# 1_Sheet_1_schdoc.net
KiCad netlist of a schematic drawn in Altium Designer
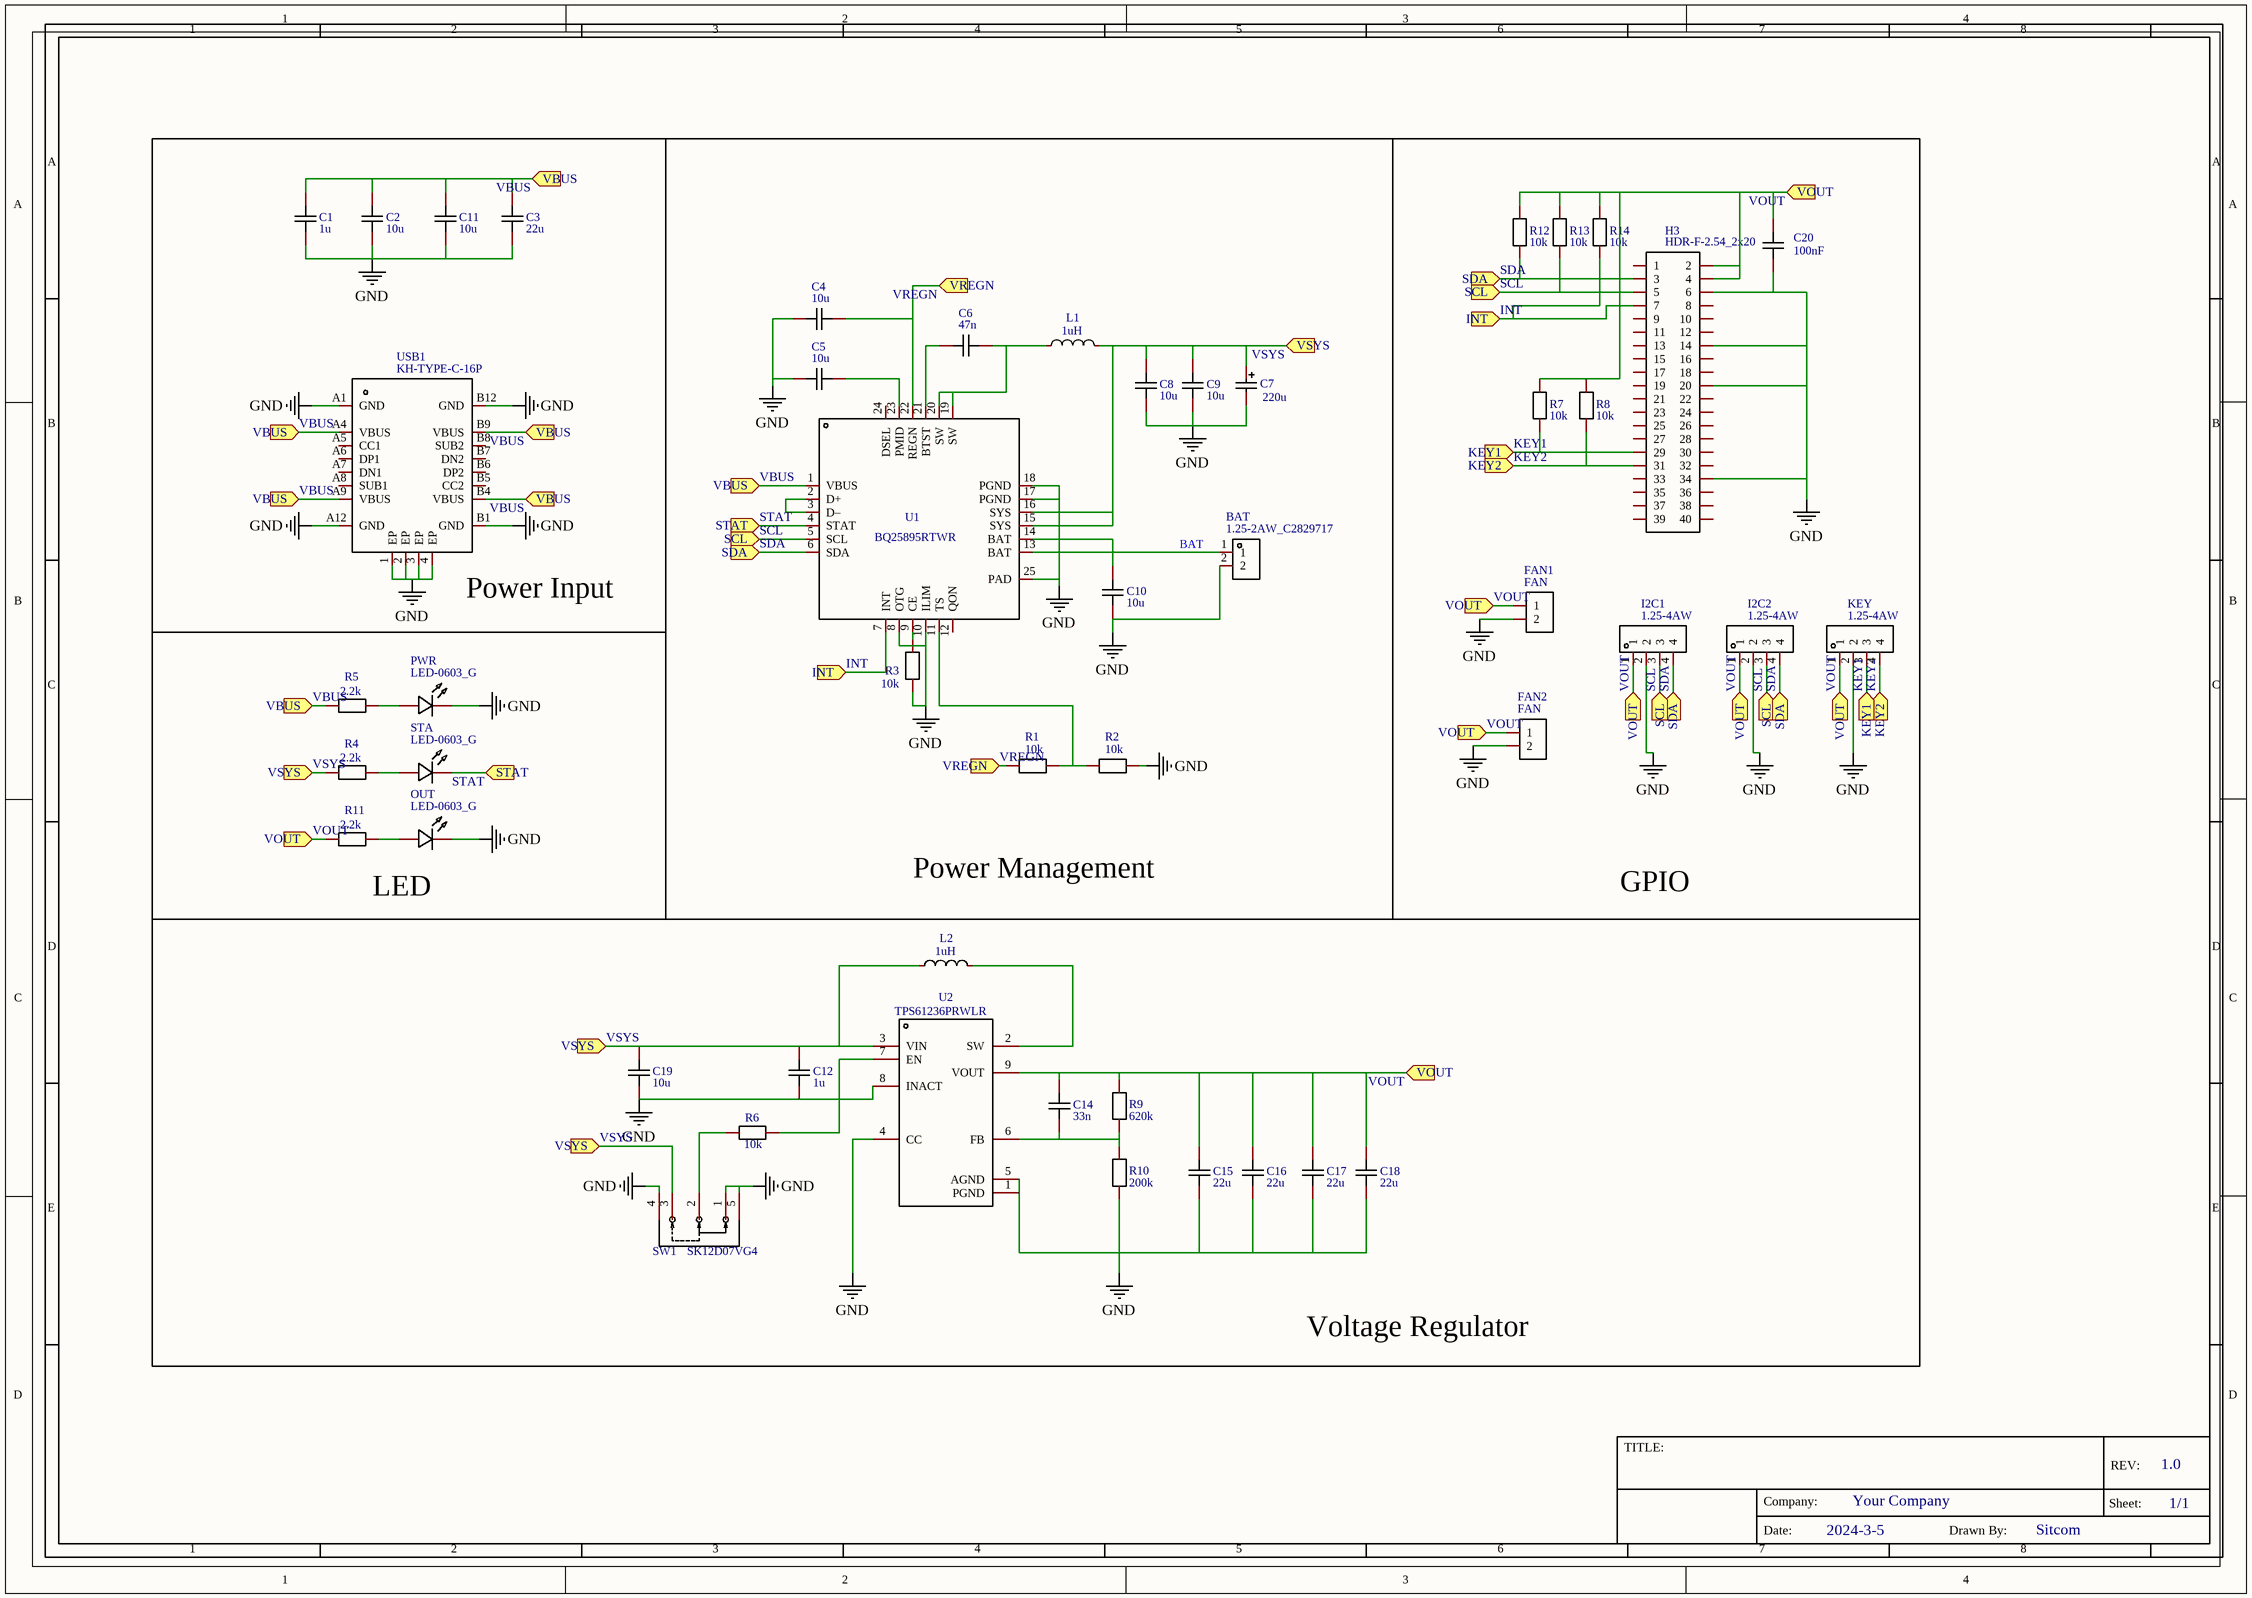
[diagram p0: 1_Sheet_1.schdoc.schdoc]

(export (version "E")
  (design (tool "Eeschema 10.0.6"))
  (components
    (comp (ref "BAT")
      (value "1.25-2AW_C2829717")
      (fields
        (field (name "NAME") "1.25-2AW_C2829717")
        (field (name "MANUFACTURER") "FG(富港)")
        (field (name "MANUFACTURER PART") "1.25-2AW")
      )
      (libsource (lib "altium-import") (part "root_0_1.25-2AW_"))
    )
    (comp (ref "C1")
      (value "1u")
      (fields (field (name "NAME") "1u"))
      (libsource (lib "altium-import") (part "root_1_1u_"))
    )
    (comp (ref "C2")
      (value "10u")
      (fields (field (name "NAME") "10u"))
      (libsource (lib "altium-import") (part "root_1_10u_"))
    )
    (comp (ref "C3")
      (value "22u")
      (fields (field (name "NAME") "22u"))
      (libsource (lib "altium-import") (part "root_1_22u_"))
    )
    (comp (ref "C4")
      (value "10u")
      (fields (field (name "NAME") "10u"))
      (libsource (lib "altium-import") (part "root_2_10u_"))
    )
    (comp (ref "C5")
      (value "10u")
      (fields (field (name "NAME") "10u"))
      (libsource (lib "altium-import") (part "root_2_10u_"))
    )
    (comp (ref "C6")
      (value "47n")
      (fields (field (name "NAME") "47n"))
      (libsource (lib "altium-import") (part "root_0_47n_"))
    )
    (comp (ref "C7")
      (value "220u")
      (fields
        (field (name "NAME") "220u")
        (field (name "MANUFACTURER") "AVX")
        (field (name "MANUFACTURER PART") "TAJB107M006RNJ")
      )
      (libsource (lib "altium-import") (part "root_1_TAJB107M006RNJ_"))
    )
    (comp (ref "C8")
      (value "10u")
      (fields (field (name "NAME") "10u"))
      (libsource (lib "altium-import") (part "root_1_10u_"))
    )
    (comp (ref "C9")
      (value "10u")
      (fields (field (name "NAME") "10u"))
      (libsource (lib "altium-import") (part "root_1_10u_"))
    )
    (comp (ref "C10")
      (value "10u")
      (fields (field (name "NAME") "10u"))
      (libsource (lib "altium-import") (part "root_1_10u_"))
    )
    (comp (ref "C11")
      (value "10u")
      (fields (field (name "NAME") "10u"))
      (libsource (lib "altium-import") (part "root_1_10u_"))
    )
    (comp (ref "C12")
      (value "1u")
      (fields (field (name "NAME") "1u"))
      (libsource (lib "altium-import") (part "root_1_1u_"))
    )
    (comp (ref "C14")
      (value "33n")
      (fields (field (name "NAME") "33n"))
      (libsource (lib "altium-import") (part "root_1_33n_"))
    )
    (comp (ref "C15")
      (value "22u")
      (fields (field (name "NAME") "22u"))
      (libsource (lib "altium-import") (part "root_1_22u_"))
    )
    (comp (ref "C16")
      (value "22u")
      (fields (field (name "NAME") "22u"))
      (libsource (lib "altium-import") (part "root_1_22u_"))
    )
    (comp (ref "C17")
      (value "22u")
      (fields (field (name "NAME") "22u"))
      (libsource (lib "altium-import") (part "root_1_22u_"))
    )
    (comp (ref "C18")
      (value "22u")
      (fields (field (name "NAME") "22u"))
      (libsource (lib "altium-import") (part "root_1_22u_"))
    )
    (comp (ref "C19")
      (value "10u")
      (fields (field (name "NAME") "10u"))
      (libsource (lib "altium-import") (part "root_1_10u_"))
    )
    (comp (ref "C20")
      (value "100nF")
      (fields (field (name "NAME") "100nF"))
      (libsource (lib "altium-import") (part "root_1_mirrored_CAP_0603_"))
    )
    (comp (ref "FAN1")
      (value "FAN")
      (fields (field (name "NAME") "FAN"))
      (libsource (lib "altium-import") (part "root_0_FAN_"))
    )
    (comp (ref "FAN2")
      (value "FAN")
      (fields (field (name "NAME") "FAN"))
      (libsource (lib "altium-import") (part "root_0_FAN_"))
    )
    (comp (ref "H3")
      (value "HDR-F-2.54_2x20")
      (fields (field (name "NAME") "HDR-F-2.54_2x20"))
      (libsource (lib "altium-import") (part "root_0_HDR-F-2.54_2x20_"))
    )
    (comp (ref "I2C1")
      (value "1.25-4AW")
      (fields (field (name "NAME") "1.25-4AW") (field (name "MANUFACTURER") "CAX"))
      (libsource (lib "altium-import") (part "root_1_1.25-4AW_"))
    )
    (comp (ref "I2C2")
      (value "1.25-4AW")
      (fields (field (name "NAME") "1.25-4AW") (field (name "MANUFACTURER") "CAX"))
      (libsource (lib "altium-import") (part "root_1_1.25-4AW_"))
    )
    (comp (ref "KEY")
      (value "1.25-4AW")
      (fields (field (name "NAME") "1.25-4AW") (field (name "MANUFACTURER") "CAX"))
      (libsource (lib "altium-import") (part "root_1_1.25-4AW_"))
    )
    (comp (ref "L1")
      (value "1uH")
      (fields
        (field (name "NAME") "1uH")
        (field (name "MANUFACTURER") "MAZO")
        (field (name "MANUFACTURER PART") "MPCA-0630-R33-M")
      )
      (libsource (lib "altium-import") (part "root_0_MPCA-0630-R33-M_"))
    )
    (comp (ref "L2")
      (value "1uH")
      (fields
        (field (name "NAME") "1uH")
        (field (name "MANUFACTURER") "MAZO")
        (field (name "MANUFACTURER PART") "MPCA-0630-R33-M")
      )
      (libsource (lib "altium-import") (part "root_0_MPCA-0630-R33-M_"))
    )
    (comp (ref "OUT")
      (value "LED-0603_G")
      (fields
        (field (name "NAME") "LED-0603_G")
        (field (name "MANUFACTURER") "EVERLIGHT(台湾亿光)")
        (field (name "MANUFACTURER PART") "19-217/GHC-YR1S2/3T")
      )
      (libsource (lib "altium-import") (part "root_0_19-217/GHC-YR1S2/3T_"))
    )
    (comp (ref "PWR")
      (value "LED-0603_G")
      (fields
        (field (name "NAME") "LED-0603_G")
        (field (name "MANUFACTURER") "EVERLIGHT(台湾亿光)")
        (field (name "MANUFACTURER PART") "19-217/GHC-YR1S2/3T")
      )
      (libsource (lib "altium-import") (part "root_0_19-217/GHC-YR1S2/3T_"))
    )
    (comp (ref "R1")
      (value "10k")
      (fields (field (name "NAME") "10k"))
      (libsource (lib "altium-import") (part "root_0_10k_"))
    )
    (comp (ref "R2")
      (value "10k")
      (fields (field (name "NAME") "10k"))
      (libsource (lib "altium-import") (part "root_0_10k_"))
    )
    (comp (ref "R3")
      (value "10k")
      (fields (field (name "NAME") "10k"))
      (libsource (lib "altium-import") (part "root_3_10k_"))
    )
    (comp (ref "R4")
      (value "2.2k")
      (fields (field (name "NAME") "2.2k"))
      (libsource (lib "altium-import") (part "root_0_2.2k_"))
    )
    (comp (ref "R5")
      (value "2.2k")
      (fields (field (name "NAME") "2.2k"))
      (libsource (lib "altium-import") (part "root_0_2.2k_"))
    )
    (comp (ref "R6")
      (value "10k")
      (fields (field (name "NAME") "10k"))
      (libsource (lib "altium-import") (part "root_0_10k_"))
    )
    (comp (ref "R7")
      (value "10k")
      (fields (field (name "NAME") "10k"))
      (libsource (lib "altium-import") (part "root_1_10k_"))
    )
    (comp (ref "R8")
      (value "10k")
      (fields (field (name "NAME") "10k"))
      (libsource (lib "altium-import") (part "root_1_10k_"))
    )
    (comp (ref "R9")
      (value "620k")
      (fields (field (name "NAME") "620k"))
      (libsource (lib "altium-import") (part "root_1_620k_"))
    )
    (comp (ref "R10")
      (value "200k")
      (fields (field (name "NAME") "200k"))
      (libsource (lib "altium-import") (part "root_1_200k_"))
    )
    (comp (ref "R11")
      (value "2.2k")
      (fields (field (name "NAME") "2.2k"))
      (libsource (lib "altium-import") (part "root_0_2.2k_"))
    )
    (comp (ref "R12")
      (value "10k")
      (fields (field (name "NAME") "10k"))
      (libsource (lib "altium-import") (part "root_1_10k_"))
    )
    (comp (ref "R13")
      (value "10k")
      (fields (field (name "NAME") "10k"))
      (libsource (lib "altium-import") (part "root_1_10k_"))
    )
    (comp (ref "R14")
      (value "10k")
      (fields (field (name "NAME") "10k"))
      (libsource (lib "altium-import") (part "root_1_10k_"))
    )
    (comp (ref "STA")
      (value "LED-0603_G")
      (fields
        (field (name "NAME") "LED-0603_G")
        (field (name "MANUFACTURER") "EVERLIGHT(台湾亿光)")
        (field (name "MANUFACTURER PART") "19-217/GHC-YR1S2/3T")
      )
      (libsource (lib "altium-import") (part "root_0_19-217/GHC-YR1S2/3T_"))
    )
    (comp (ref "SW1")
      (value "SK12D07VG4")
      (fields (field (name "NAME") "SK12D07VG4") (field (name "MANUFACTURER") "SHOU HAN"))
      (libsource (lib "altium-import") (part "root_2_SK12D07VG4_"))
    )
    (comp (ref "U1")
      (value "BQ25895RTWR")
      (fields (field (name "NAME") "BQ25895RTWR") (field (name "MANUFACTURER") "TI"))
      (libsource (lib "altium-import") (part "root_0_BQ25895RTWR_"))
    )
    (comp (ref "U2")
      (value "TPS61236PRWLR")
      (fields (field (name "NAME") "TPS61236PRWLR") (field (name "MANUFACTURER") "TI"))
      (libsource (lib "altium-import") (part "root_0_TPS61236PRWLR_"))
    )
    (comp (ref "USB1")
      (value "KH-TYPE-C-16P")
      (fields (field (name "NAME") "KH-TYPE-C-16P") (field (name "MANUFACTURER") "Shenzhen Kinghelm Elec"))
      (libsource (lib "altium-import") (part "root_0_KH-TYPE-C-16P_"))
    )
  )
  (nets
    (net (code "1") (name "/BAT") (class "Default")
      (node (ref "BAT") (pin "1") (pinfunction "1_1") (pintype "passive"))
      (node (ref "C10") (pin "2") (pinfunction "2_2") (pintype "passive"))
      (node (ref "U1") (pin "13") (pinfunction "BAT_13") (pintype "passive"))
      (node (ref "U1") (pin "14") (pinfunction "BAT_14") (pintype "passive"))
    )
    (net (code "2") (name "/INT") (class "Default")
      (node (ref "H3") (pin "7") (pinfunction "7_7") (pintype "passive"))
      (node (ref "R14") (pin "1") (pinfunction "1_1") (pintype "passive"))
      (node (ref "U1") (pin "7") (pinfunction "INT_7") (pintype "passive"))
    )
    (net (code "3") (name "/KEY1") (class "Default")
      (node (ref "H3") (pin "29") (pinfunction "29_29") (pintype "passive"))
      (node (ref "KEY") (pin "3") (pinfunction "3_3") (pintype "passive"))
      (node (ref "R7") (pin "1") (pinfunction "1_1") (pintype "passive"))
    )
    (net (code "4") (name "/KEY2") (class "Default")
      (node (ref "H3") (pin "31") (pinfunction "31_31") (pintype "passive"))
      (node (ref "KEY") (pin "4") (pinfunction "4_4") (pintype "passive"))
      (node (ref "R8") (pin "1") (pinfunction "1_1") (pintype "passive"))
    )
    (net (code "5") (name "/SCL") (class "Default")
      (node (ref "H3") (pin "5") (pinfunction "5_5") (pintype "passive"))
      (node (ref "I2C1") (pin "3") (pinfunction "3_3") (pintype "passive"))
      (node (ref "I2C2") (pin "3") (pinfunction "3_3") (pintype "passive"))
      (node (ref "R13") (pin "1") (pinfunction "1_1") (pintype "passive"))
      (node (ref "U1") (pin "5") (pinfunction "SCL_5") (pintype "passive"))
    )
    (net (code "6") (name "/SDA") (class "Default")
      (node (ref "H3") (pin "3") (pinfunction "3_3") (pintype "passive"))
      (node (ref "I2C1") (pin "4") (pinfunction "4_4") (pintype "passive"))
      (node (ref "I2C2") (pin "4") (pinfunction "4_4") (pintype "passive"))
      (node (ref "R12") (pin "1") (pinfunction "1_1") (pintype "passive"))
      (node (ref "U1") (pin "6") (pinfunction "SDA_6") (pintype "passive"))
    )
    (net (code "7") (name "/STAT") (class "Default")
      (node (ref "STA") (pin "2") (pinfunction "2_2") (pintype "passive"))
      (node (ref "U1") (pin "4") (pinfunction "STAT_4") (pintype "passive"))
    )
    (net (code "8") (name "/VBUS") (class "Default")
      (node (ref "C1") (pin "2") (pinfunction "2_2") (pintype "passive"))
      (node (ref "C11") (pin "2") (pinfunction "2_2") (pintype "passive"))
      (node (ref "C2") (pin "2") (pinfunction "2_2") (pintype "passive"))
      (node (ref "C3") (pin "2") (pinfunction "2_2") (pintype "passive"))
      (node (ref "R5") (pin "1") (pinfunction "1_1") (pintype "passive"))
      (node (ref "U1") (pin "1") (pinfunction "VBUS_1") (pintype "passive"))
      (node (ref "USB1") (pin "A4") (pinfunction "VBUS_A4") (pintype "passive"))
      (node (ref "USB1") (pin "A9") (pinfunction "VBUS_A9") (pintype "passive"))
      (node (ref "USB1") (pin "B4") (pinfunction "VBUS_B4") (pintype "passive"))
      (node (ref "USB1") (pin "B9") (pinfunction "VBUS_B9") (pintype "passive"))
    )
    (net (code "9") (name "/VOUT") (class "Default")
      (node (ref "C14") (pin "2") (pinfunction "2_2") (pintype "passive"))
      (node (ref "C15") (pin "2") (pinfunction "2_2") (pintype "passive"))
      (node (ref "C16") (pin "2") (pinfunction "2_2") (pintype "passive"))
      (node (ref "C17") (pin "2") (pinfunction "2_2") (pintype "passive"))
      (node (ref "C18") (pin "2") (pinfunction "2_2") (pintype "passive"))
      (node (ref "C20") (pin "2") (pinfunction "2_2") (pintype "passive"))
      (node (ref "FAN1") (pin "1") (pinfunction "1_1") (pintype "passive"))
      (node (ref "FAN2") (pin "1") (pinfunction "1_1") (pintype "passive"))
      (node (ref "H3") (pin "2") (pinfunction "2_2") (pintype "passive"))
      (node (ref "H3") (pin "4") (pinfunction "4_4") (pintype "passive"))
      (node (ref "I2C1") (pin "1") (pinfunction "1_1") (pintype "passive"))
      (node (ref "I2C2") (pin "1") (pinfunction "1_1") (pintype "passive"))
      (node (ref "KEY") (pin "1") (pinfunction "1_1") (pintype "passive"))
      (node (ref "R11") (pin "1") (pinfunction "1_1") (pintype "passive"))
      (node (ref "R12") (pin "2") (pinfunction "2_2") (pintype "passive"))
      (node (ref "R13") (pin "2") (pinfunction "2_2") (pintype "passive"))
      (node (ref "R14") (pin "2") (pinfunction "2_2") (pintype "passive"))
      (node (ref "R7") (pin "2") (pinfunction "2_2") (pintype "passive"))
      (node (ref "R8") (pin "2") (pinfunction "2_2") (pintype "passive"))
      (node (ref "R9") (pin "2") (pinfunction "2_2") (pintype "passive"))
      (node (ref "U2") (pin "9") (pinfunction "VOUT_9") (pintype "passive"))
    )
    (net (code "10") (name "/VREGN") (class "Default")
      (node (ref "C4") (pin "1") (pinfunction "1_1") (pintype "passive"))
      (node (ref "R1") (pin "1") (pinfunction "1_1") (pintype "passive"))
      (node (ref "U1") (pin "22") (pinfunction "REGN_22") (pintype "passive"))
    )
    (net (code "11") (name "/VSYS") (class "Default")
      (node (ref "C12") (pin "2") (pinfunction "2_2") (pintype "passive"))
      (node (ref "C19") (pin "2") (pinfunction "2_2") (pintype "passive"))
      (node (ref "C7") (pin "1") (pinfunction "1_1") (pintype "passive"))
      (node (ref "C8") (pin "2") (pinfunction "2_2") (pintype "passive"))
      (node (ref "C9") (pin "2") (pinfunction "2_2") (pintype "passive"))
      (node (ref "L1") (pin "2") (pinfunction "2_2") (pintype "passive"))
      (node (ref "L2") (pin "1") (pinfunction "1_1") (pintype "passive"))
      (node (ref "R4") (pin "1") (pinfunction "1_1") (pintype "passive"))
      (node (ref "SW1") (pin "3") (pinfunction "3_3") (pintype "passive"))
      (node (ref "U1") (pin "15") (pinfunction "SYS_15") (pintype "passive"))
      (node (ref "U1") (pin "16") (pinfunction "SYS_16") (pintype "passive"))
      (node (ref "U2") (pin "3") (pinfunction "VIN_3") (pintype "passive"))
    )
    (net (code "12") (name "GND") (class "Default")
      (node (ref "BAT") (pin "2") (pinfunction "2_2") (pintype "passive"))
      (node (ref "C1") (pin "1") (pinfunction "1_1") (pintype "passive"))
      (node (ref "C10") (pin "1") (pinfunction "1_1") (pintype "passive"))
      (node (ref "C11") (pin "1") (pinfunction "1_1") (pintype "passive"))
      (node (ref "C12") (pin "1") (pinfunction "1_1") (pintype "passive"))
      (node (ref "C15") (pin "1") (pinfunction "1_1") (pintype "passive"))
      (node (ref "C16") (pin "1") (pinfunction "1_1") (pintype "passive"))
      (node (ref "C17") (pin "1") (pinfunction "1_1") (pintype "passive"))
      (node (ref "C18") (pin "1") (pinfunction "1_1") (pintype "passive"))
      (node (ref "C19") (pin "1") (pinfunction "1_1") (pintype "passive"))
      (node (ref "C2") (pin "1") (pinfunction "1_1") (pintype "passive"))
      (node (ref "C20") (pin "1") (pinfunction "1_1") (pintype "passive"))
      (node (ref "C3") (pin "1") (pinfunction "1_1") (pintype "passive"))
      (node (ref "C4") (pin "2") (pinfunction "2_2") (pintype "passive"))
      (node (ref "C5") (pin "2") (pinfunction "2_2") (pintype "passive"))
      (node (ref "C7") (pin "2") (pinfunction "2_2") (pintype "passive"))
      (node (ref "C8") (pin "1") (pinfunction "1_1") (pintype "passive"))
      (node (ref "C9") (pin "1") (pinfunction "1_1") (pintype "passive"))
      (node (ref "FAN1") (pin "2") (pinfunction "2_2") (pintype "passive"))
      (node (ref "FAN2") (pin "2") (pinfunction "2_2") (pintype "passive"))
      (node (ref "H3") (pin "14") (pinfunction "14_14") (pintype "passive"))
      (node (ref "H3") (pin "20") (pinfunction "20_20") (pintype "passive"))
      (node (ref "H3") (pin "34") (pinfunction "34_34") (pintype "passive"))
      (node (ref "H3") (pin "6") (pinfunction "6_6") (pintype "passive"))
      (node (ref "I2C1") (pin "2") (pinfunction "2_2") (pintype "passive"))
      (node (ref "I2C2") (pin "2") (pinfunction "2_2") (pintype "passive"))
      (node (ref "KEY") (pin "2") (pinfunction "2_2") (pintype "passive"))
      (node (ref "OUT") (pin "2") (pinfunction "2_2") (pintype "passive"))
      (node (ref "PWR") (pin "2") (pinfunction "2_2") (pintype "passive"))
      (node (ref "R10") (pin "1") (pinfunction "1_1") (pintype "passive"))
      (node (ref "R2") (pin "2") (pinfunction "2_2") (pintype "passive"))
      (node (ref "R3") (pin "2") (pinfunction "2_2") (pintype "passive"))
      (node (ref "SW1") (pin "1") (pinfunction "1_1") (pintype "passive"))
      (node (ref "SW1") (pin "4") (pinfunction "4_4") (pintype "passive"))
      (node (ref "SW1") (pin "5") (pinfunction "5_5") (pintype "passive"))
      (node (ref "U1") (pin "10") (pinfunction "ILIM_10") (pintype "passive"))
      (node (ref "U1") (pin "17") (pinfunction "PGND_17") (pintype "passive"))
      (node (ref "U1") (pin "18") (pinfunction "PGND_18") (pintype "passive"))
      (node (ref "U1") (pin "25") (pinfunction "PAD_25") (pintype "passive"))
      (node (ref "U1") (pin "8") (pinfunction "OTG_8") (pintype "passive"))
      (node (ref "U2") (pin "1") (pinfunction "PGND_1") (pintype "passive"))
      (node (ref "U2") (pin "4") (pinfunction "CC_4") (pintype "passive"))
      (node (ref "U2") (pin "5") (pinfunction "AGND_5") (pintype "passive"))
      (node (ref "U2") (pin "8") (pinfunction "INACT_8") (pintype "passive"))
      (node (ref "USB1") (pin "1") (pinfunction "EP_1") (pintype "passive"))
      (node (ref "USB1") (pin "2") (pinfunction "EP_2") (pintype "passive"))
      (node (ref "USB1") (pin "3") (pinfunction "EP_3") (pintype "passive"))
      (node (ref "USB1") (pin "4") (pinfunction "EP_4") (pintype "passive"))
      (node (ref "USB1") (pin "A1") (pinfunction "GND_A1") (pintype "passive"))
      (node (ref "USB1") (pin "A12") (pinfunction "GND_A12") (pintype "passive"))
      (node (ref "USB1") (pin "B1") (pinfunction "GND_B1") (pintype "passive"))
      (node (ref "USB1") (pin "B12") (pinfunction "GND_B12") (pintype "passive"))
    )
    (net (code "13") (name "Net-(C6-Pad2)") (class "Default")
      (node (ref "C6") (pin "2") (pinfunction "2_2") (pintype "passive"))
      (node (ref "L1") (pin "1") (pinfunction "1_1") (pintype "passive"))
      (node (ref "U1") (pin "19") (pinfunction "SW_19") (pintype "passive"))
      (node (ref "U1") (pin "20") (pinfunction "SW_20") (pintype "passive"))
    )
    (net (code "14") (name "Net-(OUT-Pad1)") (class "Default")
      (node (ref "OUT") (pin "1") (pinfunction "1_1") (pintype "passive"))
      (node (ref "R11") (pin "2") (pinfunction "2_2") (pintype "passive"))
    )
    (net (code "15") (name "Net-(PWR-Pad1)") (class "Default")
      (node (ref "PWR") (pin "1") (pinfunction "1_1") (pintype "passive"))
      (node (ref "R5") (pin "2") (pinfunction "2_2") (pintype "passive"))
    )
    (net (code "16") (name "Net-(R4-Pad2)") (class "Default")
      (node (ref "R4") (pin "2") (pinfunction "2_2") (pintype "passive"))
      (node (ref "STA") (pin "1") (pinfunction "1_1") (pintype "passive"))
    )
    (net (code "17") (name "Net-(R6-Pad1)") (class "Default")
      (node (ref "R6") (pin "1") (pinfunction "1_1") (pintype "passive"))
      (node (ref "SW1") (pin "2") (pinfunction "2_2") (pintype "passive"))
    )
    (net (code "18") (name "Net-(U1-BTST)") (class "Default")
      (node (ref "C6") (pin "1") (pinfunction "1_1") (pintype "passive"))
      (node (ref "U1") (pin "21") (pinfunction "BTST_21") (pintype "passive"))
    )
    (net (code "19") (name "Net-(U1-CE)") (class "Default")
      (node (ref "R3") (pin "1") (pinfunction "1_1") (pintype "passive"))
      (node (ref "U1") (pin "9") (pinfunction "CE_9") (pintype "passive"))
    )
    (net (code "20") (name "Net-(U1-D+)") (class "Default")
      (node (ref "U1") (pin "2") (pinfunction "D+_2") (pintype "passive"))
      (node (ref "U1") (pin "3") (pinfunction "D–_3") (pintype "passive"))
    )
    (net (code "21") (name "Net-(U1-PMID)") (class "Default")
      (node (ref "C5") (pin "1") (pinfunction "1_1") (pintype "passive"))
      (node (ref "U1") (pin "23") (pinfunction "PMID_23") (pintype "passive"))
    )
    (net (code "22") (name "Net-(U1-TS)") (class "Default")
      (node (ref "R1") (pin "2") (pinfunction "2_2") (pintype "passive"))
      (node (ref "R2") (pin "1") (pinfunction "1_1") (pintype "passive"))
      (node (ref "U1") (pin "11") (pinfunction "TS_11") (pintype "passive"))
    )
    (net (code "23") (name "Net-(U2-EN)") (class "Default")
      (node (ref "R6") (pin "2") (pinfunction "2_2") (pintype "passive"))
      (node (ref "U2") (pin "7") (pinfunction "EN_7") (pintype "passive"))
    )
    (net (code "24") (name "Net-(U2-FB)") (class "Default")
      (node (ref "C14") (pin "1") (pinfunction "1_1") (pintype "passive"))
      (node (ref "R10") (pin "2") (pinfunction "2_2") (pintype "passive"))
      (node (ref "R9") (pin "1") (pinfunction "1_1") (pintype "passive"))
      (node (ref "U2") (pin "6") (pinfunction "FB_6") (pintype "passive"))
    )
    (net (code "25") (name "Net-(U2-SW)") (class "Default")
      (node (ref "L2") (pin "2") (pinfunction "2_2") (pintype "passive"))
      (node (ref "U2") (pin "2") (pinfunction "SW_2") (pintype "passive"))
    )
    (net (code "26") (name "unconnected-(H3-Pad1)") (class "Default")
      (node (ref "H3") (pin "1") (pinfunction "1_1") (pintype "passive"))
    )
    (net (code "27") (name "unconnected-(H3-Pad8)") (class "Default")
      (node (ref "H3") (pin "8") (pinfunction "8_8") (pintype "passive"))
    )
    (net (code "28") (name "unconnected-(H3-Pad9)") (class "Default")
      (node (ref "H3") (pin "9") (pinfunction "9_9") (pintype "passive"))
    )
    (net (code "29") (name "unconnected-(H3-Pad10)") (class "Default")
      (node (ref "H3") (pin "10") (pinfunction "10_10") (pintype "passive"))
    )
    (net (code "30") (name "unconnected-(H3-Pad11)") (class "Default")
      (node (ref "H3") (pin "11") (pinfunction "11_11") (pintype "passive"))
    )
    (net (code "31") (name "unconnected-(H3-Pad12)") (class "Default")
      (node (ref "H3") (pin "12") (pinfunction "12_12") (pintype "passive"))
    )
    (net (code "32") (name "unconnected-(H3-Pad13)") (class "Default")
      (node (ref "H3") (pin "13") (pinfunction "13_13") (pintype "passive"))
    )
    (net (code "33") (name "unconnected-(H3-Pad15)") (class "Default")
      (node (ref "H3") (pin "15") (pinfunction "15_15") (pintype "passive"))
    )
    (net (code "34") (name "unconnected-(H3-Pad16)") (class "Default")
      (node (ref "H3") (pin "16") (pinfunction "16_16") (pintype "passive"))
    )
    (net (code "35") (name "unconnected-(H3-Pad17)") (class "Default")
      (node (ref "H3") (pin "17") (pinfunction "17_17") (pintype "passive"))
    )
    (net (code "36") (name "unconnected-(H3-Pad18)") (class "Default")
      (node (ref "H3") (pin "18") (pinfunction "18_18") (pintype "passive"))
    )
    (net (code "37") (name "unconnected-(H3-Pad19)") (class "Default")
      (node (ref "H3") (pin "19") (pinfunction "19_19") (pintype "passive"))
    )
    (net (code "38") (name "unconnected-(H3-Pad21)") (class "Default")
      (node (ref "H3") (pin "21") (pinfunction "21_21") (pintype "passive"))
    )
    (net (code "39") (name "unconnected-(H3-Pad22)") (class "Default")
      (node (ref "H3") (pin "22") (pinfunction "22_22") (pintype "passive"))
    )
    (net (code "40") (name "unconnected-(H3-Pad23)") (class "Default")
      (node (ref "H3") (pin "23") (pinfunction "23_23") (pintype "passive"))
    )
    (net (code "41") (name "unconnected-(H3-Pad24)") (class "Default")
      (node (ref "H3") (pin "24") (pinfunction "24_24") (pintype "passive"))
    )
    (net (code "42") (name "unconnected-(H3-Pad25)") (class "Default")
      (node (ref "H3") (pin "25") (pinfunction "25_25") (pintype "passive"))
    )
    (net (code "43") (name "unconnected-(H3-Pad26)") (class "Default")
      (node (ref "H3") (pin "26") (pinfunction "26_26") (pintype "passive"))
    )
    (net (code "44") (name "unconnected-(H3-Pad27)") (class "Default")
      (node (ref "H3") (pin "27") (pinfunction "27_27") (pintype "passive"))
    )
    (net (code "45") (name "unconnected-(H3-Pad28)") (class "Default")
      (node (ref "H3") (pin "28") (pinfunction "28_28") (pintype "passive"))
    )
    (net (code "46") (name "unconnected-(H3-Pad30)") (class "Default")
      (node (ref "H3") (pin "30") (pinfunction "30_30") (pintype "passive"))
    )
    (net (code "47") (name "unconnected-(H3-Pad32)") (class "Default")
      (node (ref "H3") (pin "32") (pinfunction "32_32") (pintype "passive"))
    )
    (net (code "48") (name "unconnected-(H3-Pad33)") (class "Default")
      (node (ref "H3") (pin "33") (pinfunction "33_33") (pintype "passive"))
    )
    (net (code "49") (name "unconnected-(H3-Pad35)") (class "Default")
      (node (ref "H3") (pin "35") (pinfunction "35_35") (pintype "passive"))
    )
    (net (code "50") (name "unconnected-(H3-Pad36)") (class "Default")
      (node (ref "H3") (pin "36") (pinfunction "36_36") (pintype "passive"))
    )
    (net (code "51") (name "unconnected-(H3-Pad37)") (class "Default")
      (node (ref "H3") (pin "37") (pinfunction "37_37") (pintype "passive"))
    )
    (net (code "52") (name "unconnected-(H3-Pad38)") (class "Default")
      (node (ref "H3") (pin "38") (pinfunction "38_38") (pintype "passive"))
    )
    (net (code "53") (name "unconnected-(H3-Pad39)") (class "Default")
      (node (ref "H3") (pin "39") (pinfunction "39_39") (pintype "passive"))
    )
    (net (code "54") (name "unconnected-(H3-Pad40)") (class "Default")
      (node (ref "H3") (pin "40") (pinfunction "40_40") (pintype "passive"))
    )
    (net (code "55") (name "unconnected-(U1-DSEL-Pad24)") (class "Default")
      (node (ref "U1") (pin "24") (pinfunction "DSEL_24") (pintype "passive"))
    )
    (net (code "56") (name "unconnected-(U1-QON-Pad12)") (class "Default")
      (node (ref "U1") (pin "12") (pinfunction "QON_12") (pintype "passive"))
    )
    (net (code "57") (name "unconnected-(USB1-CC1-PadA5)") (class "Default")
      (node (ref "USB1") (pin "A5") (pinfunction "CC1_A5") (pintype "passive"))
    )
    (net (code "58") (name "unconnected-(USB1-CC2-PadB5)") (class "Default")
      (node (ref "USB1") (pin "B5") (pinfunction "CC2_B5") (pintype "passive"))
    )
    (net (code "59") (name "unconnected-(USB1-DN1-PadA7)") (class "Default")
      (node (ref "USB1") (pin "A7") (pinfunction "DN1_A7") (pintype "passive"))
    )
    (net (code "60") (name "unconnected-(USB1-DN2-PadB7)") (class "Default")
      (node (ref "USB1") (pin "B7") (pinfunction "DN2_B7") (pintype "passive"))
    )
    (net (code "61") (name "unconnected-(USB1-DP1-PadA6)") (class "Default")
      (node (ref "USB1") (pin "A6") (pinfunction "DP1_A6") (pintype "passive"))
    )
    (net (code "62") (name "unconnected-(USB1-DP2-PadB6)") (class "Default")
      (node (ref "USB1") (pin "B6") (pinfunction "DP2_B6") (pintype "passive"))
    )
    (net (code "63") (name "unconnected-(USB1-SUB1-PadA8)") (class "Default")
      (node (ref "USB1") (pin "A8") (pinfunction "SUB1_A8") (pintype "passive"))
    )
    (net (code "64") (name "unconnected-(USB1-SUB2-PadB8)") (class "Default")
      (node (ref "USB1") (pin "B8") (pinfunction "SUB2_B8") (pintype "passive"))
    )
  )
)
